# lora.net
KiCad netlist of a schematic drawn in EAGLE
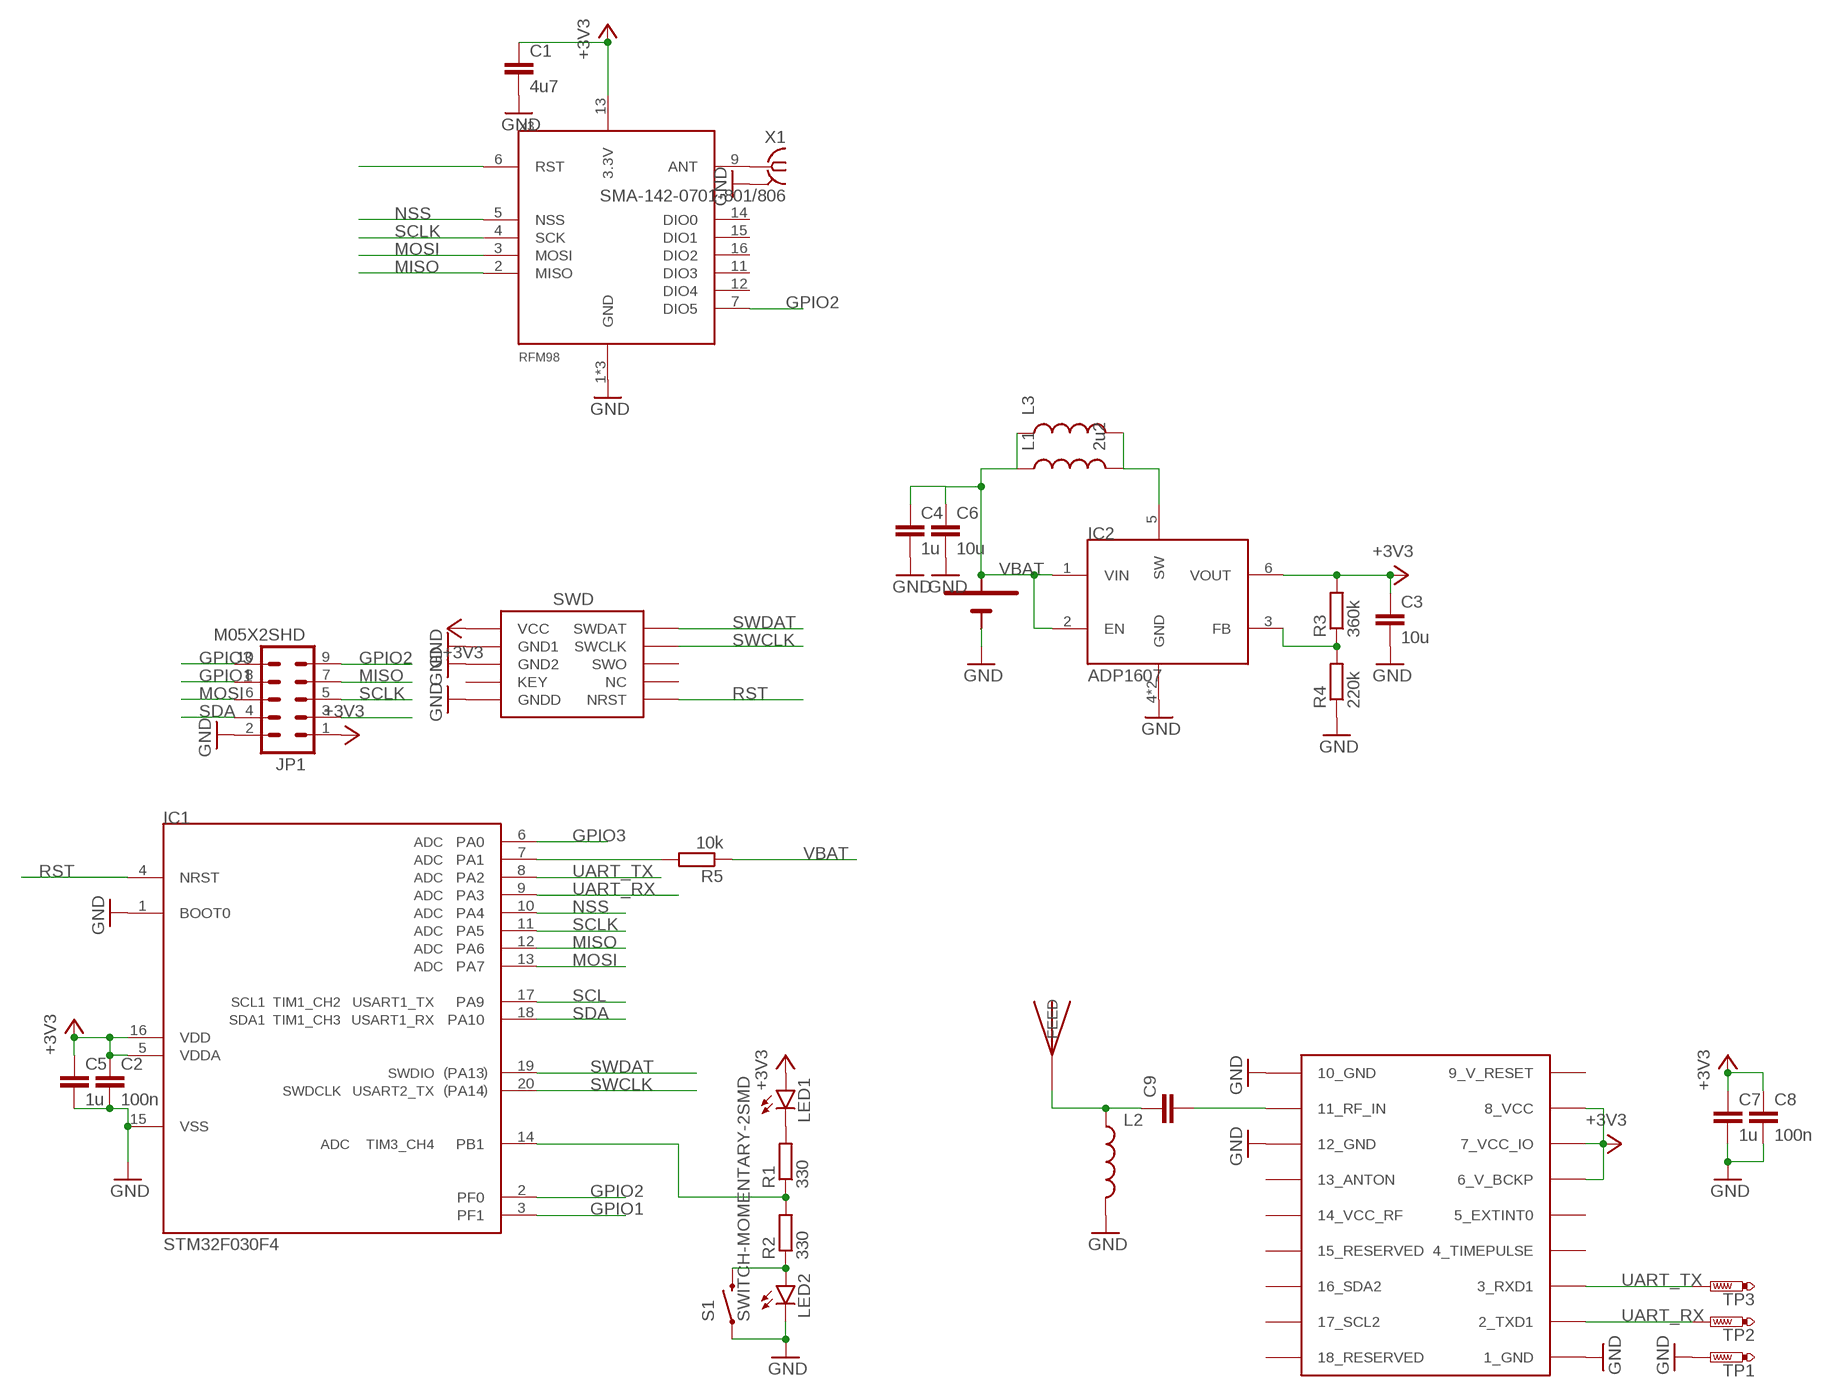
[diagram p0: schematic, sheet 1]

(export (version "E")
  (design (tool "Eeschema 10.0.6"))
  (components
    (comp (ref "C1")
      (value "4u7")
      (footprint "eagle-import:C0603")
      (libsource (lib "eagle-import") (part "C-EUC0603"))
    )
    (comp (ref "C2")
      (value "100n")
      (footprint "eagle-import:C0603")
      (libsource (lib "eagle-import") (part "C-EUC0603"))
    )
    (comp (ref "C3")
      (value "10u")
      (footprint "eagle-import:C0805")
      (libsource (lib "eagle-import") (part "C-EUC0805"))
    )
    (comp (ref "C4")
      (value "1u")
      (footprint "eagle-import:C0603")
      (libsource (lib "eagle-import") (part "C-EUC0603"))
    )
    (comp (ref "C5")
      (value "1u")
      (footprint "eagle-import:C0603")
      (libsource (lib "eagle-import") (part "C-EUC0603"))
    )
    (comp (ref "C6")
      (value "10u")
      (footprint "eagle-import:C0805")
      (libsource (lib "eagle-import") (part "C-EUC0805"))
    )
    (comp (ref "C7")
      (value "1u")
      (footprint "eagle-import:C0603")
      (libsource (lib "eagle-import") (part "C-EUC0603"))
    )
    (comp (ref "C8")
      (value "100n")
      (footprint "eagle-import:C0603")
      (libsource (lib "eagle-import") (part "C-EUC0603"))
    )
    (comp (ref "C9")
      (value "C-EUC0603")
      (footprint "eagle-import:C0603")
      (libsource (lib "eagle-import") (part "C-EUC0603"))
    )
    (comp (ref "IC1")
      (value "STM32F030F4")
      (footprint "eagle-import:TSSOP20")
      (libsource (lib "eagle-import") (part "STM32F030F4"))
    )
    (comp (ref "IC2")
      (value "ADP1607")
      (footprint "eagle-import:LFCSP6")
      (libsource (lib "eagle-import") (part "ADP1607"))
    )
    (comp (ref "J1")
      (value "SWD_PTH_SHROUD")
      (footprint "eagle-import:SWD_PTH_SHROUD")
      (libsource (lib "eagle-import") (part "SWD_PTH_SHROUD"))
    )
    (comp (ref "JP1")
      (value "M05X2SHD")
      (footprint "eagle-import:2X5-SHROUDED")
      (libsource (lib "eagle-import") (part "M05X2SHD"))
    )
    (comp (ref "L1")
      (value "2u2")
      (footprint "eagle-import:0805")
      (libsource (lib "eagle-import") (part "INDUCTOR0805"))
    )
    (comp (ref "L2")
      (value "INDUCTOR0603")
      (footprint "eagle-import:0603")
      (libsource (lib "eagle-import") (part "INDUCTOR0603"))
    )
    (comp (ref "L3")
      (value "INDUCTOR1210")
      (footprint "eagle-import:1210")
      (libsource (lib "eagle-import") (part "INDUCTOR1210"))
    )
    (comp (ref "LED1")
      (value "LED0603")
      (footprint "eagle-import:LED-0603")
      (libsource (lib "eagle-import") (part "LED0603"))
    )
    (comp (ref "LED2")
      (value "LED0603")
      (footprint "eagle-import:LED-0603")
      (libsource (lib "eagle-import") (part "LED0603"))
    )
    (comp (ref "R1")
      (value "330")
      (footprint "eagle-import:R0603")
      (libsource (lib "eagle-import") (part "R-EU_R0603"))
    )
    (comp (ref "R2")
      (value "330")
      (footprint "eagle-import:R0603")
      (libsource (lib "eagle-import") (part "R-EU_R0603"))
    )
    (comp (ref "R3")
      (value "360k")
      (footprint "eagle-import:R0603")
      (libsource (lib "eagle-import") (part "R-EU_R0603"))
    )
    (comp (ref "R4")
      (value "220k")
      (footprint "eagle-import:R0603")
      (libsource (lib "eagle-import") (part "R-EU_R0603"))
    )
    (comp (ref "R5")
      (value "10k")
      (footprint "eagle-import:R0603")
      (libsource (lib "eagle-import") (part "R-EU_R0603"))
    )
    (comp (ref "S1")
      (value "SWITCH-MOMENTARY-2SMD")
      (footprint "eagle-import:TACTILE_SWITCH_SMD")
      (libsource (lib "eagle-import") (part "SWITCH-MOMENTARY-2SMD"))
    )
    (comp (ref "TP1")
      (value "PTR1B1,27")
      (footprint "eagle-import:B1,27")
      (libsource (lib "eagle-import") (part "PTR1B1,27"))
    )
    (comp (ref "TP2")
      (value "PTR1B1,27")
      (footprint "eagle-import:B1,27")
      (libsource (lib "eagle-import") (part "PTR1B1,27"))
    )
    (comp (ref "TP3")
      (value "PTR1B1,27")
      (footprint "eagle-import:B1,27")
      (libsource (lib "eagle-import") (part "PTR1B1,27"))
    )
    (comp (ref "U$5")
      (value "JTI_ANTENNA-1575AT43A40")
      (footprint "eagle-import:JTI_ANTENNA-1575AT43A40")
      (libsource (lib "eagle-import") (part "JTI_ANTENNA-1575AT43A40"))
    )
    (comp (ref "U$6")
      (value "KEYSTONE-53")
      (footprint "eagle-import:KEYSTONE53")
      (libsource (lib "eagle-import") (part "KEYSTONE-53"))
    )
    (comp (ref "X1")
      (value "SMA-142-0701-801/806")
      (footprint "eagle-import:J502-ND-142-0701-801_806")
      (fields (field (name "MF") "JOHNSON COMPONENTS") (field (name "MPN") "142-0701-801"))
      (libsource (lib "eagle-import") (part "SMA-142-0701-801/806"))
    )
    (comp (ref "X2")
      (value "UBLOX_MAX")
      (footprint "eagle-import:UBLOX_MAX")
      (libsource (lib "eagle-import") (part "UBLOX_MAX"))
    )
    (comp (ref "X3")
      (value "RFM98")
      (footprint "eagle-import:RFM97")
      (libsource (lib "eagle-import") (part "RFM98"))
    )
  )
  (nets
    (net (code "1") (name "+3V3") (class "Default")
      (node (ref "C1") (pin "1") (pinfunction "1_1") (pintype "passive"))
      (node (ref "C2") (pin "1") (pinfunction "1_1") (pintype "passive"))
      (node (ref "C3") (pin "1") (pinfunction "1_1") (pintype "passive"))
      (node (ref "C5") (pin "1") (pinfunction "1_1") (pintype "passive"))
      (node (ref "C7") (pin "1") (pinfunction "1_1") (pintype "passive"))
      (node (ref "C8") (pin "1") (pinfunction "1_1") (pintype "passive"))
      (node (ref "IC1") (pin "16") (pinfunction "VDD_16") (pintype "power_in"))
      (node (ref "IC1") (pin "5") (pinfunction "VDDA_5") (pintype "power_in"))
      (node (ref "IC2") (pin "6") (pinfunction "VOUT_6") (pintype "output"))
      (node (ref "J1") (pin "1") (pinfunction "VCC_1") (pintype "power_in"))
      (node (ref "JP1") (pin "1") (pinfunction "1_1") (pintype "passive"))
      (node (ref "LED1") (pin "A") (pinfunction "A_A") (pintype "passive"))
      (node (ref "R3") (pin "2") (pinfunction "2_2") (pintype "passive"))
      (node (ref "X2") (pin "6_V_BCKP") (pinfunction "6_V_BCKP_6_V_BCKP") (pintype "bidirectional"))
      (node (ref "X2") (pin "7_VCC_IO") (pinfunction "7_VCC_IO_7_VCC_IO") (pintype "power_in"))
      (node (ref "X2") (pin "8_VCC") (pinfunction "8_VCC_8_VCC") (pintype "power_in"))
      (node (ref "X3") (pin "13") (pinfunction "3.3V_13") (pintype "power_in"))
    )
    (net (code "2") (name "/9_V_RESET") (class "Default")
      (node (ref "X2") (pin "9_V_RESET") (pinfunction "9_V_RESET_9_V_RESET") (pintype "power_in"))
    )
    (net (code "3") (name "/GPIO1") (class "Default")
      (node (ref "IC1") (pin "3") (pinfunction "PF1_3") (pintype "bidirectional"))
      (node (ref "JP1") (pin "8") (pinfunction "8_8") (pintype "passive"))
    )
    (net (code "4") (name "/GPIO2") (class "Default")
      (node (ref "IC1") (pin "2") (pinfunction "PF0_2") (pintype "bidirectional"))
      (node (ref "JP1") (pin "9") (pinfunction "9_9") (pintype "passive"))
      (node (ref "X3") (pin "7") (pinfunction "DIO5_7") (pintype "bidirectional"))
    )
    (net (code "5") (name "/GPIO3") (class "Default")
      (node (ref "IC1") (pin "6") (pinfunction "PA0_6") (pintype "bidirectional"))
      (node (ref "JP1") (pin "10") (pinfunction "10_10") (pintype "passive"))
    )
    (net (code "6") (name "/MISO") (class "Default")
      (node (ref "IC1") (pin "12") (pinfunction "PA6_12") (pintype "bidirectional"))
      (node (ref "JP1") (pin "7") (pinfunction "7_7") (pintype "passive"))
      (node (ref "X3") (pin "2") (pinfunction "MISO_2") (pintype "output"))
    )
    (net (code "7") (name "/MOSI") (class "Default")
      (node (ref "IC1") (pin "13") (pinfunction "PA7_13") (pintype "bidirectional"))
      (node (ref "JP1") (pin "6") (pinfunction "6_6") (pintype "passive"))
      (node (ref "X3") (pin "3") (pinfunction "MOSI_3") (pintype "input"))
    )
    (net (code "8") (name "/NSS") (class "Default")
      (node (ref "IC1") (pin "10") (pinfunction "PA4_10") (pintype "bidirectional"))
      (node (ref "X3") (pin "5") (pinfunction "NSS_5") (pintype "input"))
    )
    (net (code "9") (name "/RST") (class "Default")
      (node (ref "IC1") (pin "4") (pinfunction "NRST_4") (pintype "input"))
      (node (ref "J1") (pin "10") (pinfunction "NRST_10") (pintype "bidirectional"))
    )
    (net (code "10") (name "/SCL") (class "Default")
      (node (ref "IC1") (pin "17") (pinfunction "PA9_17") (pintype "bidirectional"))
      (node (ref "JP1") (pin "3") (pinfunction "3_3") (pintype "passive"))
    )
    (net (code "11") (name "/SCLK") (class "Default")
      (node (ref "IC1") (pin "11") (pinfunction "PA5_11") (pintype "bidirectional"))
      (node (ref "JP1") (pin "5") (pinfunction "5_5") (pintype "passive"))
      (node (ref "X3") (pin "4") (pinfunction "SCK_4") (pintype "input"))
    )
    (net (code "12") (name "/SDA") (class "Default")
      (node (ref "IC1") (pin "18") (pinfunction "PA10_18") (pintype "bidirectional"))
      (node (ref "JP1") (pin "4") (pinfunction "4_4") (pintype "passive"))
    )
    (net (code "13") (name "/SWCLK") (class "Default")
      (node (ref "IC1") (pin "20") (pinfunction "PA14_20") (pintype "bidirectional"))
      (node (ref "J1") (pin "4") (pinfunction "SWCLK_4") (pintype "bidirectional"))
    )
    (net (code "14") (name "/SWDAT") (class "Default")
      (node (ref "IC1") (pin "19") (pinfunction "PA13_19") (pintype "bidirectional"))
      (node (ref "J1") (pin "2") (pinfunction "SWDAT_2") (pintype "bidirectional"))
    )
    (net (code "15") (name "/UART_RX") (class "Default")
      (node (ref "IC1") (pin "9") (pinfunction "PA3_9") (pintype "bidirectional"))
      (node (ref "TP2") (pin "TP") (pinfunction "TP_TP") (pintype "input"))
      (node (ref "X2") (pin "2_TXD1") (pinfunction "2_TXD1_2_TXD1") (pintype "bidirectional"))
    )
    (net (code "16") (name "/UART_TX") (class "Default")
      (node (ref "IC1") (pin "8") (pinfunction "PA2_8") (pintype "bidirectional"))
      (node (ref "TP3") (pin "TP") (pinfunction "TP_TP") (pintype "input"))
      (node (ref "X2") (pin "3_RXD1") (pinfunction "3_RXD1_3_RXD1") (pintype "bidirectional"))
    )
    (net (code "17") (name "/VBAT") (class "Default")
      (node (ref "C4") (pin "1") (pinfunction "1_1") (pintype "passive"))
      (node (ref "C6") (pin "1") (pinfunction "1_1") (pintype "passive"))
      (node (ref "IC2") (pin "1") (pinfunction "VIN_1") (pintype "input"))
      (node (ref "IC2") (pin "2") (pinfunction "EN_2") (pintype "input"))
      (node (ref "L1") (pin "1") (pinfunction "1_1") (pintype "passive"))
      (node (ref "L3") (pin "1") (pinfunction "1_1") (pintype "passive"))
      (node (ref "R5") (pin "1") (pinfunction "1_1") (pintype "passive"))
      (node (ref "U$6") (pin "P1") (pinfunction "+_P1") (pintype "passive"))
      (node (ref "U$6") (pin "P2") (pinfunction "+_P2") (pintype "passive"))
    )
    (net (code "18") (name "GND") (class "Default")
      (node (ref "C1") (pin "2") (pinfunction "2_2") (pintype "passive"))
      (node (ref "C2") (pin "2") (pinfunction "2_2") (pintype "passive"))
      (node (ref "C3") (pin "2") (pinfunction "2_2") (pintype "passive"))
      (node (ref "C4") (pin "2") (pinfunction "2_2") (pintype "passive"))
      (node (ref "C5") (pin "2") (pinfunction "2_2") (pintype "passive"))
      (node (ref "C6") (pin "2") (pinfunction "2_2") (pintype "passive"))
      (node (ref "C7") (pin "2") (pinfunction "2_2") (pintype "passive"))
      (node (ref "C8") (pin "2") (pinfunction "2_2") (pintype "passive"))
      (node (ref "IC1") (pin "1") (pinfunction "BOOT0_1") (pintype "input"))
      (node (ref "IC1") (pin "15") (pinfunction "VSS_15") (pintype "power_in"))
      (node (ref "IC2") (pin "4") (pinfunction "GND_4") (pintype "power_in"))
      (node (ref "IC2") (pin "EP") (pinfunction "GND_EP") (pintype "power_in"))
      (node (ref "J1") (pin "3") (pinfunction "GND1_3") (pintype "power_in"))
      (node (ref "J1") (pin "5") (pinfunction "GND2_5") (pintype "power_in"))
      (node (ref "J1") (pin "9") (pinfunction "GNDD_9") (pintype "power_in"))
      (node (ref "JP1") (pin "2") (pinfunction "2_2") (pintype "passive"))
      (node (ref "L2") (pin "2") (pinfunction "2_2") (pintype "passive"))
      (node (ref "LED2") (pin "C") (pinfunction "C_C") (pintype "passive"))
      (node (ref "R4") (pin "1") (pinfunction "1_1") (pintype "passive"))
      (node (ref "S1") (pin "1") (pinfunction "1_1") (pintype "passive"))
      (node (ref "TP1") (pin "TP") (pinfunction "TP_TP") (pintype "input"))
      (node (ref "U$6") (pin "N1") (pinfunction "-_N1") (pintype "passive"))
      (node (ref "U$6") (pin "N2") (pinfunction "-_N2") (pintype "passive"))
      (node (ref "X1") (pin "G@1") (pinfunction "2_G@1") (pintype "passive"))
      (node (ref "X1") (pin "G@2") (pinfunction "2_G@2") (pintype "passive"))
      (node (ref "X1") (pin "G@3") (pinfunction "2_G@3") (pintype "passive"))
      (node (ref "X1") (pin "G@4") (pinfunction "2_G@4") (pintype "passive"))
      (node (ref "X2") (pin "10_GND") (pinfunction "10_GND_10_GND") (pintype "power_in"))
      (node (ref "X2") (pin "12_GND") (pinfunction "12_GND_12_GND") (pintype "power_in"))
      (node (ref "X2") (pin "1_GND") (pinfunction "1_GND_1_GND") (pintype "power_in"))
      (node (ref "X3") (pin "1") (pinfunction "GND_1") (pintype "power_in"))
      (node (ref "X3") (pin "10") (pinfunction "GND_10") (pintype "power_in"))
      (node (ref "X3") (pin "8") (pinfunction "GND_8") (pintype "power_in"))
    )
    (net (code "19") (name "Net-(C9-Pad1)") (class "Default")
      (node (ref "C9") (pin "1") (pinfunction "1_1") (pintype "passive"))
      (node (ref "L2") (pin "1") (pinfunction "1_1") (pintype "passive"))
      (node (ref "U$5") (pin "FEED") (pinfunction "FEED_FEED") (pintype "bidirectional"))
    )
    (net (code "20") (name "Net-(C9-Pad2)") (class "Default")
      (node (ref "C9") (pin "2") (pinfunction "2_2") (pintype "passive"))
      (node (ref "X2") (pin "11_RF_IN") (pinfunction "11_RF_IN_11_RF_IN") (pintype "bidirectional"))
    )
    (net (code "21") (name "Net-(IC1-PA1)") (class "Default")
      (node (ref "IC1") (pin "7") (pinfunction "PA1_7") (pintype "bidirectional"))
      (node (ref "R5") (pin "2") (pinfunction "2_2") (pintype "passive"))
    )
    (net (code "22") (name "Net-(IC1-PB1)") (class "Default")
      (node (ref "IC1") (pin "14") (pinfunction "PB1_14") (pintype "bidirectional"))
      (node (ref "R1") (pin "1") (pinfunction "1_1") (pintype "passive"))
      (node (ref "R2") (pin "2") (pinfunction "2_2") (pintype "passive"))
    )
    (net (code "23") (name "Net-(IC2-FB)") (class "Default")
      (node (ref "IC2") (pin "3") (pinfunction "FB_3") (pintype "input"))
      (node (ref "R3") (pin "1") (pinfunction "1_1") (pintype "passive"))
      (node (ref "R4") (pin "2") (pinfunction "2_2") (pintype "passive"))
    )
    (net (code "24") (name "Net-(IC2-SW)") (class "Default")
      (node (ref "IC2") (pin "5") (pinfunction "SW_5") (pintype "input"))
      (node (ref "L1") (pin "2") (pinfunction "2_2") (pintype "passive"))
      (node (ref "L3") (pin "2") (pinfunction "2_2") (pintype "passive"))
    )
    (net (code "25") (name "Net-(LED1-PadC)") (class "Default")
      (node (ref "LED1") (pin "C") (pinfunction "C_C") (pintype "passive"))
      (node (ref "R1") (pin "2") (pinfunction "2_2") (pintype "passive"))
    )
    (net (code "26") (name "Net-(S1-2)") (class "Default")
      (node (ref "LED2") (pin "A") (pinfunction "A_A") (pintype "passive"))
      (node (ref "R2") (pin "1") (pinfunction "1_1") (pintype "passive"))
      (node (ref "S1") (pin "3") (pinfunction "2_3") (pintype "passive"))
    )
    (net (code "27") (name "Net-(X3-ANT)") (class "Default")
      (node (ref "X1") (pin "1") (pinfunction "1_1") (pintype "passive"))
      (node (ref "X3") (pin "9") (pinfunction "ANT_9") (pintype "bidirectional"))
    )
    (net (code "28") (name "unconnected-(J1-KEY-Pad7)") (class "Default")
      (node (ref "J1") (pin "7") (pinfunction "KEY_7") (pintype "bidirectional"))
    )
    (net (code "29") (name "unconnected-(J1-NC-Pad8)") (class "Default")
      (node (ref "J1") (pin "8") (pinfunction "NC_8") (pintype "no_connect"))
    )
    (net (code "30") (name "unconnected-(J1-SWO-Pad6)") (class "Default")
      (node (ref "J1") (pin "6") (pinfunction "SWO_6") (pintype "bidirectional"))
    )
    (net (code "31") (name "unconnected-(X2-Pad4_TIMEPULSE)") (class "Default")
      (node (ref "X2") (pin "4_TIMEPULSE") (pinfunction "4_TIMEPULSE_4_TIMEPULSE") (pintype "bidirectional"))
    )
    (net (code "32") (name "unconnected-(X2-Pad5_EXTINT0)") (class "Default")
      (node (ref "X2") (pin "5_EXTINT0") (pinfunction "5_EXTINT0_5_EXTINT0") (pintype "bidirectional"))
    )
    (net (code "33") (name "unconnected-(X2-Pad13_ANTON)") (class "Default")
      (node (ref "X2") (pin "13_ANTON") (pinfunction "13_ANTON_13_ANTON") (pintype "bidirectional"))
    )
    (net (code "34") (name "unconnected-(X2-Pad14_VCC_RF)") (class "Default")
      (node (ref "X2") (pin "14_VCC_RF") (pinfunction "14_VCC_RF_14_VCC_RF") (pintype "bidirectional"))
    )
    (net (code "35") (name "unconnected-(X2-Pad15_RESERVED)") (class "Default")
      (node (ref "X2") (pin "15_RESERVED") (pinfunction "15_RESERVED_15_RESERVED") (pintype "bidirectional"))
    )
    (net (code "36") (name "unconnected-(X2-Pad16_SDA2)") (class "Default")
      (node (ref "X2") (pin "16_SDA2") (pinfunction "16_SDA2_16_SDA2") (pintype "bidirectional"))
    )
    (net (code "37") (name "unconnected-(X2-Pad17_SCL2)") (class "Default")
      (node (ref "X2") (pin "17_SCL2") (pinfunction "17_SCL2_17_SCL2") (pintype "bidirectional"))
    )
    (net (code "38") (name "unconnected-(X2-Pad18_RESERVED)") (class "Default")
      (node (ref "X2") (pin "18_RESERVED") (pinfunction "18_RESERVED_18_RESERVED") (pintype "bidirectional"))
    )
    (net (code "39") (name "unconnected-(X3-DIO0-Pad14)") (class "Default")
      (node (ref "X3") (pin "14") (pinfunction "DIO0_14") (pintype "bidirectional"))
    )
    (net (code "40") (name "unconnected-(X3-DIO1-Pad15)") (class "Default")
      (node (ref "X3") (pin "15") (pinfunction "DIO1_15") (pintype "bidirectional"))
    )
    (net (code "41") (name "unconnected-(X3-DIO2-Pad16)") (class "Default")
      (node (ref "X3") (pin "16") (pinfunction "DIO2_16") (pintype "bidirectional"))
    )
    (net (code "42") (name "unconnected-(X3-DIO3-Pad11)") (class "Default")
      (node (ref "X3") (pin "11") (pinfunction "DIO3_11") (pintype "bidirectional"))
    )
    (net (code "43") (name "unconnected-(X3-DIO4-Pad12)") (class "Default")
      (node (ref "X3") (pin "12") (pinfunction "DIO4_12") (pintype "bidirectional"))
    )
    (net (code "44") (name "unconnected-(X3-RST-Pad6)") (class "Default")
      (node (ref "X3") (pin "6") (pinfunction "RST_6") (pintype "input"))
    )
  )
)
